# rfIMU.net
KiCad netlist of a schematic drawn in EAGLE
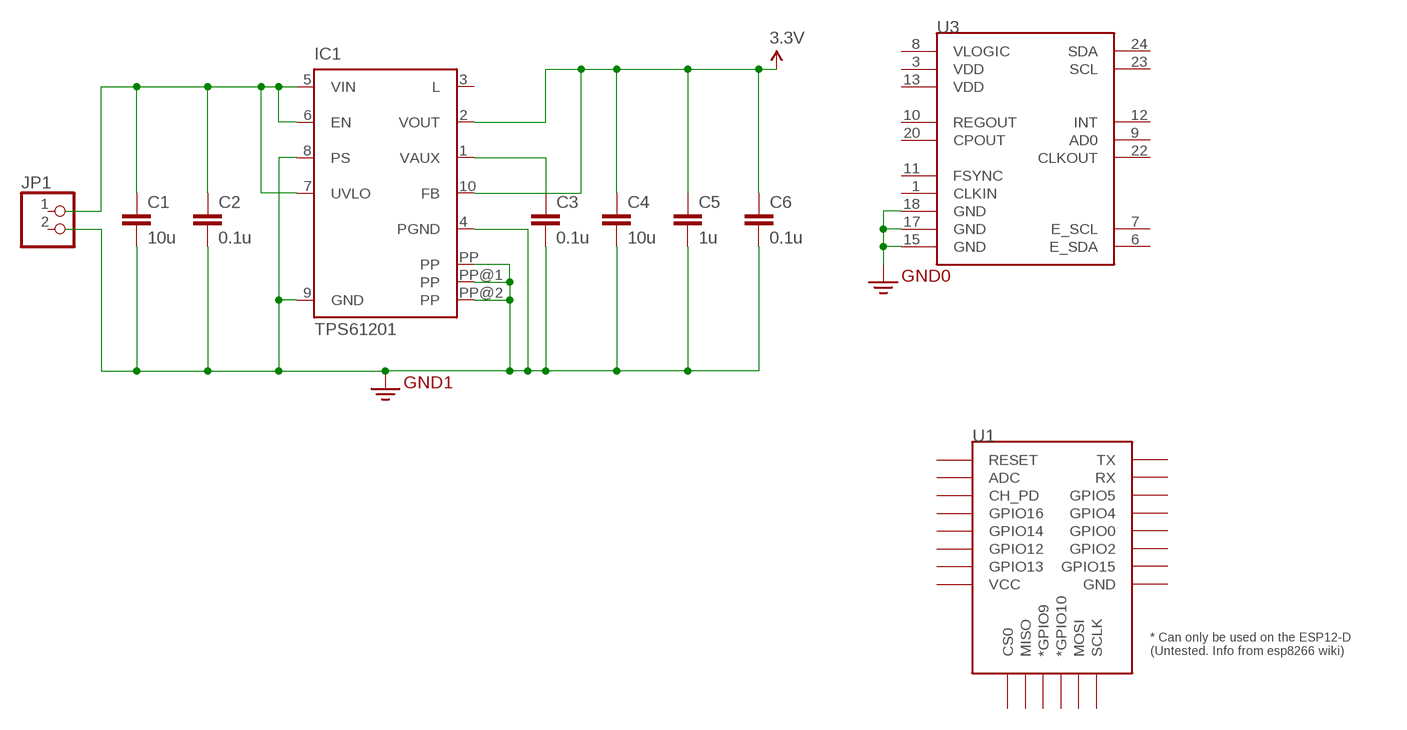
[diagram p0: schematic, sheet 1]

(export (version "E")
  (design (tool "Eeschema 10.0.6"))
  (components
    (comp (ref "C1")
      (value "10u")
      (footprint "eagle-import:0603")
      (libsource (lib "eagle-import") (part "CAP0603"))
    )
    (comp (ref "C2")
      (value "0.1u")
      (footprint "eagle-import:0603")
      (libsource (lib "eagle-import") (part "CAP0603"))
    )
    (comp (ref "C3")
      (value "0.1u")
      (footprint "eagle-import:0603")
      (libsource (lib "eagle-import") (part "CAP0603"))
    )
    (comp (ref "C4")
      (value "10u")
      (footprint "eagle-import:0603")
      (libsource (lib "eagle-import") (part "CAP0603"))
    )
    (comp (ref "C5")
      (value "1u")
      (footprint "eagle-import:0603")
      (libsource (lib "eagle-import") (part "CAP0603"))
    )
    (comp (ref "C6")
      (value "0.1u")
      (footprint "eagle-import:0603")
      (libsource (lib "eagle-import") (part "CAP0603"))
    )
    (comp (ref "IC1")
      (value "TPS61201")
      (footprint "eagle-import:S-PDSO-N10")
      (fields (field (name "MPN") "TPS61201DRCT"))
      (libsource (lib "eagle-import") (part "TPS61201"))
    )
    (comp (ref "JP1")
      (value "PINHD-1X2")
      (footprint "eagle-import:1X02")
      (libsource (lib "eagle-import") (part "PINHD-1X2"))
    )
    (comp (ref "U1")
      (value "ESP12ESMD")
      (footprint "eagle-import:ESP12E-SMD")
      (libsource (lib "eagle-import") (part "ESP12ESMD"))
    )
    (comp (ref "U3")
      (value "MPU-9150QFN-24-NP")
      (footprint "eagle-import:QFN-24-NP")
      (libsource (lib "eagle-import") (part "MPU-9150QFN-24-NP"))
    )
  )
  (nets
    (net (code "1") (name "3.3V") (class "Default")
      (node (ref "C1") (pin "2") (pinfunction "2_2") (pintype "passive"))
      (node (ref "C2") (pin "2") (pinfunction "2_2") (pintype "passive"))
      (node (ref "C3") (pin "2") (pinfunction "2_2") (pintype "passive"))
      (node (ref "C4") (pin "1") (pinfunction "1_1") (pintype "passive"))
      (node (ref "C4") (pin "2") (pinfunction "2_2") (pintype "passive"))
      (node (ref "C5") (pin "1") (pinfunction "1_1") (pintype "passive"))
      (node (ref "C5") (pin "2") (pinfunction "2_2") (pintype "passive"))
      (node (ref "C6") (pin "1") (pinfunction "1_1") (pintype "passive"))
      (node (ref "C6") (pin "2") (pinfunction "2_2") (pintype "passive"))
      (node (ref "IC1") (pin "10") (pinfunction "FB_10") (pintype "input"))
      (node (ref "IC1") (pin "2") (pinfunction "VOUT_2") (pintype "passive"))
      (node (ref "IC1") (pin "4") (pinfunction "PGND_4") (pintype "power_in"))
      (node (ref "IC1") (pin "8") (pinfunction "PS_8") (pintype "input"))
      (node (ref "IC1") (pin "9") (pinfunction "GND_9") (pintype "power_in"))
      (node (ref "IC1") (pin "PP") (pinfunction "PP_PP") (pintype "power_in"))
      (node (ref "IC1") (pin "PP@1") (pinfunction "PP_PP@1") (pintype "power_in"))
      (node (ref "IC1") (pin "PP@2") (pinfunction "PP_PP@2") (pintype "power_in"))
      (node (ref "U3") (pin "15") (pinfunction "GND_15") (pintype "bidirectional"))
      (node (ref "U3") (pin "17") (pinfunction "GND_17") (pintype "bidirectional"))
      (node (ref "U3") (pin "18") (pinfunction "GND_18") (pintype "bidirectional"))
    )
    (net (code "2") (name "Net-(IC1-EN)") (class "Default")
      (node (ref "C1") (pin "1") (pinfunction "1_1") (pintype "passive"))
      (node (ref "C2") (pin "1") (pinfunction "1_1") (pintype "passive"))
      (node (ref "IC1") (pin "5") (pinfunction "VIN_5") (pintype "input"))
      (node (ref "IC1") (pin "6") (pinfunction "EN_6") (pintype "input"))
      (node (ref "IC1") (pin "7") (pinfunction "UVLO_7") (pintype "input"))
    )
    (net (code "3") (name "Net-(IC1-VAUX)") (class "Default")
      (node (ref "C3") (pin "1") (pinfunction "1_1") (pintype "passive"))
      (node (ref "IC1") (pin "1") (pinfunction "VAUX_1") (pintype "bidirectional"))
    )
    (net (code "4") (name "unconnected-(IC1-L-Pad3)") (class "Default")
      (node (ref "IC1") (pin "3") (pinfunction "L_3") (pintype "input"))
    )
    (net (code "5") (name "unconnected-(JP1-Pad1)") (class "Default")
      (node (ref "JP1") (pin "1") (pinfunction "1_1") (pintype "passive"))
    )
    (net (code "6") (name "unconnected-(JP1-Pad2)") (class "Default")
      (node (ref "JP1") (pin "2") (pinfunction "2_2") (pintype "passive"))
    )
    (net (code "7") (name "unconnected-(U1-*GPIO9-PadGPIO9)") (class "Default")
      (node (ref "U1") (pin "GPIO9") (pinfunction "*GPIO9_GPIO9") (pintype "bidirectional"))
    )
    (net (code "8") (name "unconnected-(U1-*GPIO10-PadGPIO10)") (class "Default")
      (node (ref "U1") (pin "GPIO10") (pinfunction "*GPIO10_GPIO10") (pintype "bidirectional"))
    )
    (net (code "9") (name "unconnected-(U1-PadADC)") (class "Default")
      (node (ref "U1") (pin "ADC") (pinfunction "ADC_ADC") (pintype "bidirectional"))
    )
    (net (code "10") (name "unconnected-(U1-PadCH_PD)") (class "Default")
      (node (ref "U1") (pin "CH_PD") (pinfunction "CH_PD_CH_PD") (pintype "bidirectional"))
    )
    (net (code "11") (name "unconnected-(U1-PadCS0)") (class "Default")
      (node (ref "U1") (pin "CS0") (pinfunction "CS0_CS0") (pintype "bidirectional"))
    )
    (net (code "12") (name "unconnected-(U1-PadGND)") (class "Default")
      (node (ref "U1") (pin "GND") (pinfunction "GND_GND") (pintype "bidirectional"))
    )
    (net (code "13") (name "unconnected-(U1-PadGPIO0)") (class "Default")
      (node (ref "U1") (pin "GPIO0") (pinfunction "GPIO0_GPIO0") (pintype "bidirectional"))
    )
    (net (code "14") (name "unconnected-(U1-PadGPIO2)") (class "Default")
      (node (ref "U1") (pin "GPIO2") (pinfunction "GPIO2_GPIO2") (pintype "bidirectional"))
    )
    (net (code "15") (name "unconnected-(U1-PadGPIO4)") (class "Default")
      (node (ref "U1") (pin "GPIO4") (pinfunction "GPIO4_GPIO4") (pintype "bidirectional"))
    )
    (net (code "16") (name "unconnected-(U1-PadGPIO5)") (class "Default")
      (node (ref "U1") (pin "GPIO5") (pinfunction "GPIO5_GPIO5") (pintype "bidirectional"))
    )
    (net (code "17") (name "unconnected-(U1-PadGPIO12)") (class "Default")
      (node (ref "U1") (pin "GPIO12") (pinfunction "GPIO12_GPIO12") (pintype "bidirectional"))
    )
    (net (code "18") (name "unconnected-(U1-PadGPIO13)") (class "Default")
      (node (ref "U1") (pin "GPIO13") (pinfunction "GPIO13_GPIO13") (pintype "bidirectional"))
    )
    (net (code "19") (name "unconnected-(U1-PadGPIO14)") (class "Default")
      (node (ref "U1") (pin "GPIO14") (pinfunction "GPIO14_GPIO14") (pintype "bidirectional"))
    )
    (net (code "20") (name "unconnected-(U1-PadGPIO15)") (class "Default")
      (node (ref "U1") (pin "GPIO15") (pinfunction "GPIO15_GPIO15") (pintype "bidirectional"))
    )
    (net (code "21") (name "unconnected-(U1-PadGPIO16)") (class "Default")
      (node (ref "U1") (pin "GPIO16") (pinfunction "GPIO16_GPIO16") (pintype "bidirectional"))
    )
    (net (code "22") (name "unconnected-(U1-PadMISO)") (class "Default")
      (node (ref "U1") (pin "MISO") (pinfunction "MISO_MISO") (pintype "bidirectional"))
    )
    (net (code "23") (name "unconnected-(U1-PadMOSI)") (class "Default")
      (node (ref "U1") (pin "MOSI") (pinfunction "MOSI_MOSI") (pintype "bidirectional"))
    )
    (net (code "24") (name "unconnected-(U1-PadRESET)") (class "Default")
      (node (ref "U1") (pin "RESET") (pinfunction "RESET_RESET") (pintype "bidirectional"))
    )
    (net (code "25") (name "unconnected-(U1-PadSCLK)") (class "Default")
      (node (ref "U1") (pin "SCLK") (pinfunction "SCLK_SCLK") (pintype "bidirectional"))
    )
    (net (code "26") (name "unconnected-(U1-PadVCC)") (class "Default")
      (node (ref "U1") (pin "VCC") (pinfunction "VCC_VCC") (pintype "bidirectional"))
    )
    (net (code "27") (name "unconnected-(U1-RX-PadRXD0)") (class "Default")
      (node (ref "U1") (pin "RXD0") (pinfunction "RX_RXD0") (pintype "bidirectional"))
    )
    (net (code "28") (name "unconnected-(U1-TX-PadTXD0)") (class "Default")
      (node (ref "U1") (pin "TXD0") (pinfunction "TX_TXD0") (pintype "bidirectional"))
    )
    (net (code "29") (name "unconnected-(U3-AD0-Pad9)") (class "Default")
      (node (ref "U3") (pin "9") (pinfunction "AD0_9") (pintype "bidirectional"))
    )
    (net (code "30") (name "unconnected-(U3-CLKIN-Pad1)") (class "Default")
      (node (ref "U3") (pin "1") (pinfunction "CLKIN_1") (pintype "bidirectional"))
    )
    (net (code "31") (name "unconnected-(U3-CLKOUT-Pad22)") (class "Default")
      (node (ref "U3") (pin "22") (pinfunction "CLKOUT_22") (pintype "bidirectional"))
    )
    (net (code "32") (name "unconnected-(U3-CPOUT-Pad20)") (class "Default")
      (node (ref "U3") (pin "20") (pinfunction "CPOUT_20") (pintype "bidirectional"))
    )
    (net (code "33") (name "unconnected-(U3-E_SCL-Pad7)") (class "Default")
      (node (ref "U3") (pin "7") (pinfunction "E_SCL_7") (pintype "bidirectional"))
    )
    (net (code "34") (name "unconnected-(U3-E_SDA-Pad6)") (class "Default")
      (node (ref "U3") (pin "6") (pinfunction "E_SDA_6") (pintype "bidirectional"))
    )
    (net (code "35") (name "unconnected-(U3-FSYNC-Pad11)") (class "Default")
      (node (ref "U3") (pin "11") (pinfunction "FSYNC_11") (pintype "bidirectional"))
    )
    (net (code "36") (name "unconnected-(U3-INT-Pad12)") (class "Default")
      (node (ref "U3") (pin "12") (pinfunction "INT_12") (pintype "bidirectional"))
    )
    (net (code "37") (name "unconnected-(U3-REGOUT-Pad10)") (class "Default")
      (node (ref "U3") (pin "10") (pinfunction "REGOUT_10") (pintype "bidirectional"))
    )
    (net (code "38") (name "unconnected-(U3-SCL-Pad23)") (class "Default")
      (node (ref "U3") (pin "23") (pinfunction "SCL_23") (pintype "bidirectional"))
    )
    (net (code "39") (name "unconnected-(U3-SDA-Pad24)") (class "Default")
      (node (ref "U3") (pin "24") (pinfunction "SDA_24") (pintype "bidirectional"))
    )
    (net (code "40") (name "unconnected-(U3-VDD-Pad3)") (class "Default")
      (node (ref "U3") (pin "3") (pinfunction "VDD_3") (pintype "bidirectional"))
    )
    (net (code "41") (name "unconnected-(U3-VDD-Pad13)") (class "Default")
      (node (ref "U3") (pin "13") (pinfunction "VDD_13") (pintype "bidirectional"))
    )
    (net (code "42") (name "unconnected-(U3-VLOGIC-Pad8)") (class "Default")
      (node (ref "U3") (pin "8") (pinfunction "VLOGIC_8") (pintype "bidirectional"))
    )
  )
)
